# rone12_to_rone13.net
KiCad netlist of a schematic drawn in Altium Designer
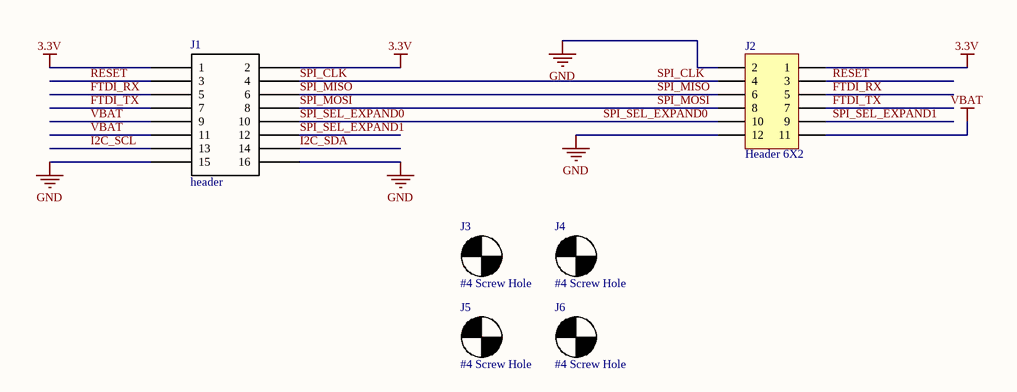
[diagram p0: rone12_to_rone13.SchDoc]

(export (version "E")
  (design (tool "Eeschema 10.0.6"))
  (components
    (comp (ref "J1")
      (value "header")
      (footprint "HEADERSM 8X2")
      (libsource (lib "mrone") (part "HEADER 8X2"))
    )
    (comp (ref "J2")
      (value "Header 6X2")
      (footprint "HDR2X6")
      (description "Header, 6-Pin, Dual row")
      (fields (field (name "PUBLISHER") "Altium Limited"))
      (libsource (lib "Miscellaneous Connectors") (part "Header 6X2"))
    )
    (comp (ref "J3")
      (value "#4 Screw Hole")
      (footprint "#4_Screw_Hole")
      (description "A mechanical hole for mounting the board")
      (libsource (lib "mrone") (part "Mechanical_Hole"))
    )
    (comp (ref "J4")
      (value "#4 Screw Hole")
      (footprint "#4_Screw_Hole")
      (description "A mechanical hole for mounting the board")
      (libsource (lib "mrone") (part "Mechanical_Hole"))
    )
    (comp (ref "J5")
      (value "#4 Screw Hole")
      (footprint "#4_Screw_Hole")
      (description "A mechanical hole for mounting the board")
      (libsource (lib "mrone") (part "Mechanical_Hole"))
    )
    (comp (ref "J6")
      (value "#4 Screw Hole")
      (footprint "#4_Screw_Hole")
      (description "A mechanical hole for mounting the board")
      (libsource (lib "mrone") (part "Mechanical_Hole"))
    )
  )
  (nets
    (net (code "1") (name "/FTDI_RX") (class "Default")
      (node (ref "J1") (pin "5") (pinfunction "5_5") (pintype "passive"))
      (node (ref "J2") (pin "5") (pinfunction "5_5") (pintype "passive"))
    )
    (net (code "2") (name "/FTDI_TX") (class "Default")
      (node (ref "J1") (pin "7") (pinfunction "7_7") (pintype "passive"))
      (node (ref "J2") (pin "7") (pinfunction "7_7") (pintype "passive"))
    )
    (net (code "3") (name "/I2C_SCL") (class "Default")
      (node (ref "J1") (pin "13") (pinfunction "13_13") (pintype "passive"))
    )
    (net (code "4") (name "/I2C_SDA") (class "Default")
      (node (ref "J1") (pin "14") (pinfunction "14_14") (pintype "passive"))
    )
    (net (code "5") (name "/RESET") (class "Default")
      (node (ref "J1") (pin "3") (pinfunction "3_3") (pintype "passive"))
      (node (ref "J2") (pin "3") (pinfunction "3_3") (pintype "passive"))
    )
    (net (code "6") (name "/SPI_CLK") (class "Default")
      (node (ref "J1") (pin "4") (pinfunction "4_4") (pintype "passive"))
      (node (ref "J2") (pin "4") (pinfunction "4_4") (pintype "passive"))
    )
    (net (code "7") (name "/SPI_MISO") (class "Default")
      (node (ref "J1") (pin "6") (pinfunction "6_6") (pintype "passive"))
      (node (ref "J2") (pin "6") (pinfunction "6_6") (pintype "passive"))
    )
    (net (code "8") (name "/SPI_MOSI") (class "Default")
      (node (ref "J1") (pin "8") (pinfunction "8_8") (pintype "passive"))
      (node (ref "J2") (pin "8") (pinfunction "8_8") (pintype "passive"))
    )
    (net (code "9") (name "/SPI_SEL_EXPAND0") (class "Default")
      (node (ref "J1") (pin "10") (pinfunction "10_10") (pintype "passive"))
      (node (ref "J2") (pin "10") (pinfunction "10_10") (pintype "passive"))
    )
    (net (code "10") (name "/SPI_SEL_EXPAND1") (class "Default")
      (node (ref "J1") (pin "12") (pinfunction "12_12") (pintype "passive"))
      (node (ref "J2") (pin "9") (pinfunction "9_9") (pintype "passive"))
    )
    (net (code "11") (name "3.3V") (class "Default")
      (node (ref "J1") (pin "1") (pinfunction "1_1") (pintype "passive"))
      (node (ref "J1") (pin "2") (pinfunction "2_2") (pintype "passive"))
      (node (ref "J2") (pin "1") (pinfunction "1_1") (pintype "passive"))
    )
    (net (code "12") (name "GND") (class "Default")
      (node (ref "J1") (pin "15") (pinfunction "15_15") (pintype "passive"))
      (node (ref "J1") (pin "16") (pinfunction "16_16") (pintype "passive"))
      (node (ref "J2") (pin "12") (pinfunction "12_12") (pintype "passive"))
      (node (ref "J2") (pin "2") (pinfunction "2_2") (pintype "passive"))
    )
    (net (code "13") (name "VBAT") (class "Default")
      (node (ref "J1") (pin "11") (pinfunction "11_11") (pintype "passive"))
      (node (ref "J1") (pin "9") (pinfunction "9_9") (pintype "passive"))
      (node (ref "J2") (pin "11") (pinfunction "11_11") (pintype "passive"))
    )
  )
)
